# Sheet1.net
KiCad netlist of a schematic drawn in Altium Designer
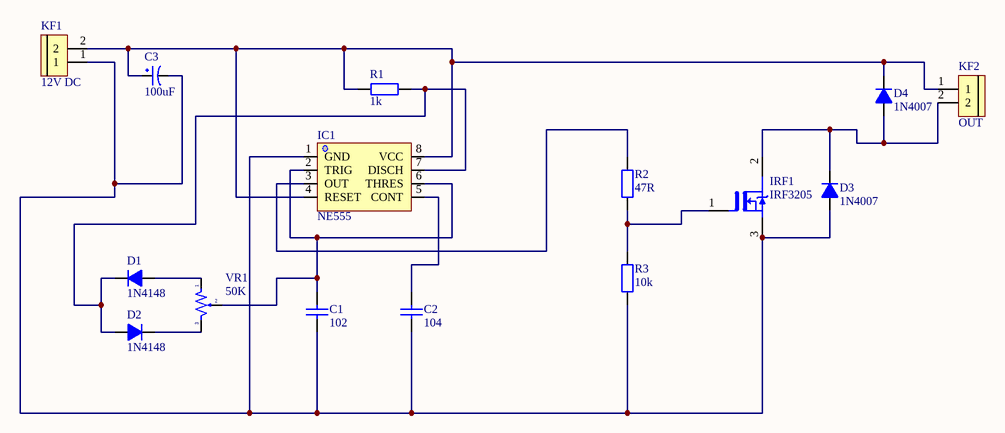
[diagram p0: Sheet1.SchDoc]

(export (version "E")
  (design (tool "Eeschema 10.0.6"))
  (components
    (comp (ref "C1")
      (value "102")
      (footprint "tu gom")
      (description "Cắm")
      (libsource (lib "Capacitor") (part "Tu gom 102 50V"))
    )
    (comp (ref "C2")
      (value "104")
      (footprint "tu gom")
      (description "Cắm")
      (libsource (lib "Capacitor") (part "Tu gom 104 50V"))
    )
    (comp (ref "C3")
      (value "100uF")
      (footprint "tu hoa 5mm")
      (description "Cắm")
      (libsource (lib "Capacitor") (part "Tu Hoa 100uF 25V 6x11"))
    )
    (comp (ref "D1")
      (value "1N4148")
      (footprint "DIODE 0.5A")
      (description "Cắm")
      (libsource (lib "Diode") (part "Diode 1N4148"))
    )
    (comp (ref "D2")
      (value "1N4148")
      (footprint "DIODE 0.5A")
      (description "Cắm")
      (libsource (lib "Diode") (part "Diode 1N4148"))
    )
    (comp (ref "D3")
      (value "1N4007")
      (footprint "DIODE 1A")
      (description "Cắm")
      (libsource (lib "Diode") (part "Diode 1N4007"))
    )
    (comp (ref "D4")
      (value "1N4007")
      (footprint "DIODE 1A")
      (description "Cắm")
      (libsource (lib "Diode") (part "Diode 1N4007"))
    )
    (comp (ref "IC1")
      (value "NE555")
      (footprint "DIP8/W0.3")
      (libsource (lib "SCH_Lib_Devzone") (part "NE555"))
    )
    (comp (ref "IRF1")
      (value "IRF3205")
      (footprint "QTO-220")
      (libsource (lib "SCH_Lib_Devzone") (part "IRF3205"))
    )
    (comp (ref "KF1")
      (value "12V DC")
      (footprint "Con 2 KF301 5.08")
      (description "Cắm")
      (libsource (lib "Connector") (part "CON 2 KF301"))
    )
    (comp (ref "KF2")
      (value "OUT")
      (footprint "Con 2 KF301 5.08")
      (description "Cắm")
      (libsource (lib "") (part "CON 2 KF301_1"))
    )
    (comp (ref "R1")
      (value "1k")
      (footprint "tro vach 1/4w")
      (description "Cắm")
      (libsource (lib "Resistor") (part "Tro Vach 1/4W 5% 1k"))
    )
    (comp (ref "R2")
      (value "47R")
      (footprint "tro vach 1/4w")
      (description "Cắm")
      (libsource (lib "Resistor") (part "Tro Vach 1/4W 5% 47R"))
    )
    (comp (ref "R3")
      (value "10k")
      (footprint "tro vach 1/4w")
      (description "Căm")
      (libsource (lib "Resistor") (part "Tro Vach 1/4W 5% 10k"))
    )
    (comp (ref "VR1")
      (value "50K")
      (footprint "Bien Tro Volume Don")
      (description "Cắm")
      (libsource (lib "Resistor") (part "Triet Ap Don 50k"))
    )
  )
  (nets
    (net (code "1") (name "Net-(D1-A)") (class "Default")
      (node (ref "D1") (pin "1") (pinfunction "A_1") (pintype "passive"))
      (node (ref "VR1") (pin "1") (pinfunction "1_1") (pintype "passive"))
    )
    (net (code "2") (name "Net-(D1-K)") (class "Default")
      (node (ref "D1") (pin "2") (pinfunction "K_2") (pintype "passive"))
      (node (ref "D2") (pin "1") (pinfunction "A_1") (pintype "passive"))
      (node (ref "IC1") (pin "7") (pinfunction "DISCH_7") (pintype "passive"))
      (node (ref "R1") (pin "2") (pinfunction "2_2") (pintype "passive"))
    )
    (net (code "3") (name "Net-(D2-K)") (class "Default")
      (node (ref "D2") (pin "2") (pinfunction "K_2") (pintype "passive"))
      (node (ref "VR1") (pin "3") (pinfunction "3_3") (pintype "passive"))
    )
    (net (code "4") (name "Net-(D3-A)") (class "Default")
      (node (ref "C1") (pin "2") (pinfunction "2_2") (pintype "passive"))
      (node (ref "C2") (pin "2") (pinfunction "2_2") (pintype "passive"))
      (node (ref "C3") (pin "2") (pinfunction "2_2") (pintype "passive"))
      (node (ref "D3") (pin "1") (pinfunction "A_1") (pintype "passive"))
      (node (ref "IC1") (pin "1") (pinfunction "GND_1") (pintype "passive"))
      (node (ref "IRF1") (pin "3") (pinfunction "S_3") (pintype "passive"))
      (node (ref "KF1") (pin "1") (pinfunction "1_1") (pintype "passive"))
      (node (ref "R3") (pin "1") (pinfunction "1_1") (pintype "passive"))
    )
    (net (code "5") (name "Net-(D3-K)") (class "Default")
      (node (ref "D3") (pin "2") (pinfunction "K_2") (pintype "passive"))
      (node (ref "D4") (pin "1") (pinfunction "A_1") (pintype "passive"))
      (node (ref "IRF1") (pin "2") (pinfunction "D_2") (pintype "passive"))
      (node (ref "KF2") (pin "2") (pinfunction "2_2") (pintype "passive"))
    )
    (net (code "6") (name "Net-(D4-K)") (class "Default")
      (node (ref "C3") (pin "1") (pinfunction "1_1") (pintype "passive"))
      (node (ref "D4") (pin "2") (pinfunction "K_2") (pintype "passive"))
      (node (ref "IC1") (pin "4") (pinfunction "RESET_4") (pintype "passive"))
      (node (ref "IC1") (pin "8") (pinfunction "VCC_8") (pintype "passive"))
      (node (ref "KF1") (pin "2") (pinfunction "2_2") (pintype "passive"))
      (node (ref "KF2") (pin "1") (pinfunction "1_1") (pintype "passive"))
      (node (ref "R1") (pin "1") (pinfunction "1_1") (pintype "passive"))
    )
    (net (code "7") (name "Net-(IC1-CONT)") (class "Default")
      (node (ref "C2") (pin "1") (pinfunction "1_1") (pintype "passive"))
      (node (ref "IC1") (pin "5") (pinfunction "CONT_5") (pintype "passive"))
    )
    (net (code "8") (name "Net-(IC1-OUT)") (class "Default")
      (node (ref "IC1") (pin "3") (pinfunction "OUT_3") (pintype "passive"))
      (node (ref "R2") (pin "1") (pinfunction "1_1") (pintype "passive"))
    )
    (net (code "9") (name "Net-(IC1-THRES)") (class "Default")
      (node (ref "C1") (pin "1") (pinfunction "1_1") (pintype "passive"))
      (node (ref "IC1") (pin "2") (pinfunction "TRIG_2") (pintype "passive"))
      (node (ref "IC1") (pin "6") (pinfunction "THRES_6") (pintype "passive"))
      (node (ref "VR1") (pin "2") (pinfunction "2_2") (pintype "passive"))
    )
    (net (code "10") (name "Net-(IRF1-G)") (class "Default")
      (node (ref "IRF1") (pin "1") (pinfunction "G_1") (pintype "passive"))
      (node (ref "R2") (pin "2") (pinfunction "2_2") (pintype "passive"))
      (node (ref "R3") (pin "2") (pinfunction "2_2") (pintype "passive"))
    )
  )
)
